# TestPoints.net
KiCad netlist of a schematic drawn in Altium Designer
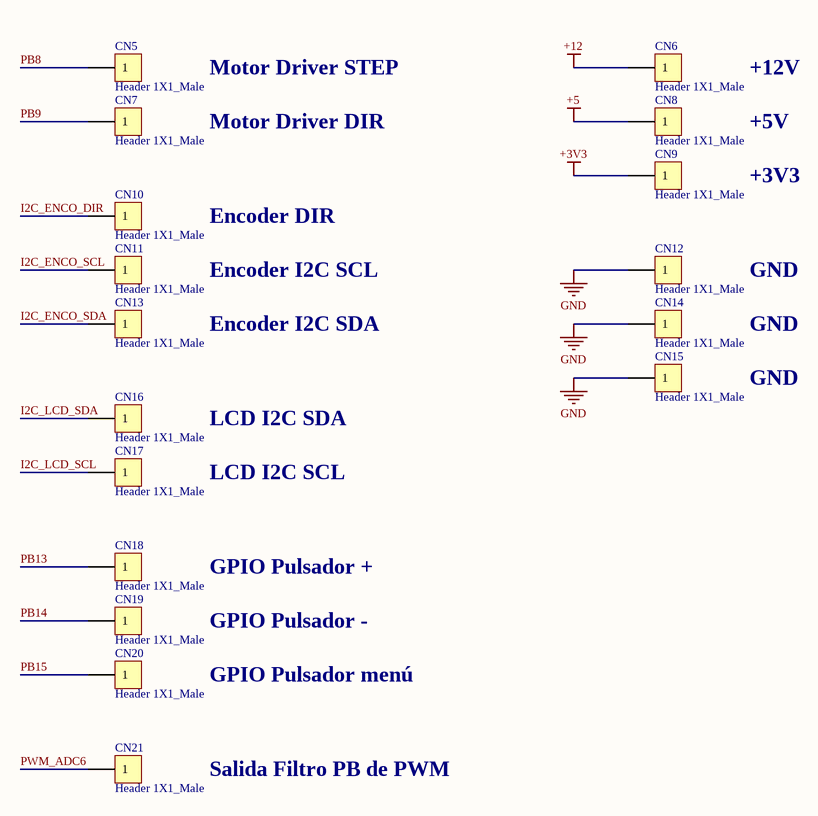
[diagram p0: TestPoints.SchDoc]

(export (version "E")
  (design (tool "Eeschema 10.0.6"))
  (components
    (comp (ref "CN5")
      (value "Header 1X1_Male")
      (footprint "1*1P_MALE")
      (description "Header, 1-Pin, Single row,male")
      (fields (field (name "PUBLISHER") "Altium Limited"))
      (libsource (lib "ProyectoTD3") (part "Header 1X1_Male"))
    )
    (comp (ref "CN6")
      (value "Header 1X1_Male")
      (footprint "1*1P_MALE")
      (description "Header, 1-Pin, Single row,male")
      (fields (field (name "PUBLISHER") "Altium Limited"))
      (libsource (lib "ProyectoTD3") (part "Header 1X1_Male"))
    )
    (comp (ref "CN7")
      (value "Header 1X1_Male")
      (footprint "1*1P_MALE")
      (description "Header, 1-Pin, Single row,male")
      (fields (field (name "PUBLISHER") "Altium Limited"))
      (libsource (lib "ProyectoTD3") (part "Header 1X1_Male"))
    )
    (comp (ref "CN8")
      (value "Header 1X1_Male")
      (footprint "1*1P_MALE")
      (description "Header, 1-Pin, Single row,male")
      (fields (field (name "PUBLISHER") "Altium Limited"))
      (libsource (lib "ProyectoTD3") (part "Header 1X1_Male"))
    )
    (comp (ref "CN9")
      (value "Header 1X1_Male")
      (footprint "1*1P_MALE")
      (description "Header, 1-Pin, Single row,male")
      (fields (field (name "PUBLISHER") "Altium Limited"))
      (libsource (lib "ProyectoTD3") (part "Header 1X1_Male"))
    )
    (comp (ref "CN10")
      (value "Header 1X1_Male")
      (footprint "1*1P_MALE")
      (description "Header, 1-Pin, Single row,male")
      (fields (field (name "PUBLISHER") "Altium Limited"))
      (libsource (lib "ProyectoTD3") (part "Header 1X1_Male"))
    )
    (comp (ref "CN11")
      (value "Header 1X1_Male")
      (footprint "1*1P_MALE")
      (description "Header, 1-Pin, Single row,male")
      (fields (field (name "PUBLISHER") "Altium Limited"))
      (libsource (lib "ProyectoTD3") (part "Header 1X1_Male"))
    )
    (comp (ref "CN12")
      (value "Header 1X1_Male")
      (footprint "1*1P_MALE")
      (description "Header, 1-Pin, Single row,male")
      (fields (field (name "PUBLISHER") "Altium Limited"))
      (libsource (lib "ProyectoTD3") (part "Header 1X1_Male"))
    )
    (comp (ref "CN13")
      (value "Header 1X1_Male")
      (footprint "1*1P_MALE")
      (description "Header, 1-Pin, Single row,male")
      (fields (field (name "PUBLISHER") "Altium Limited"))
      (libsource (lib "ProyectoTD3") (part "Header 1X1_Male"))
    )
    (comp (ref "CN14")
      (value "Header 1X1_Male")
      (footprint "1*1P_MALE")
      (description "Header, 1-Pin, Single row,male")
      (fields (field (name "PUBLISHER") "Altium Limited"))
      (libsource (lib "ProyectoTD3") (part "Header 1X1_Male"))
    )
    (comp (ref "CN15")
      (value "Header 1X1_Male")
      (footprint "1*1P_MALE")
      (description "Header, 1-Pin, Single row,male")
      (fields (field (name "PUBLISHER") "Altium Limited"))
      (libsource (lib "ProyectoTD3") (part "Header 1X1_Male"))
    )
    (comp (ref "CN16")
      (value "Header 1X1_Male")
      (footprint "1*1P_MALE")
      (description "Header, 1-Pin, Single row,male")
      (fields (field (name "PUBLISHER") "Altium Limited"))
      (libsource (lib "ProyectoTD3") (part "Header 1X1_Male"))
    )
    (comp (ref "CN17")
      (value "Header 1X1_Male")
      (footprint "1*1P_MALE")
      (description "Header, 1-Pin, Single row,male")
      (fields (field (name "PUBLISHER") "Altium Limited"))
      (libsource (lib "ProyectoTD3") (part "Header 1X1_Male"))
    )
    (comp (ref "CN18")
      (value "Header 1X1_Male")
      (footprint "1*1P_MALE")
      (description "Header, 1-Pin, Single row,male")
      (fields (field (name "PUBLISHER") "Altium Limited"))
      (libsource (lib "ProyectoTD3") (part "Header 1X1_Male"))
    )
    (comp (ref "CN19")
      (value "Header 1X1_Male")
      (footprint "1*1P_MALE")
      (description "Header, 1-Pin, Single row,male")
      (fields (field (name "PUBLISHER") "Altium Limited"))
      (libsource (lib "ProyectoTD3") (part "Header 1X1_Male"))
    )
    (comp (ref "CN20")
      (value "Header 1X1_Male")
      (footprint "1*1P_MALE")
      (description "Header, 1-Pin, Single row,male")
      (fields (field (name "PUBLISHER") "Altium Limited"))
      (libsource (lib "ProyectoTD3") (part "Header 1X1_Male"))
    )
    (comp (ref "CN21")
      (value "Header 1X1_Male")
      (footprint "1*1P_MALE")
      (description "Header, 1-Pin, Single row,male")
      (fields (field (name "PUBLISHER") "Altium Limited"))
      (libsource (lib "ProyectoTD3") (part "Header 1X1_Male"))
    )
  )
  (nets
    (net (code "1") (name "+3V3") (class "Default")
      (node (ref "CN9") (pin "1") (pinfunction "1_1") (pintype "passive"))
    )
    (net (code "2") (name "+5") (class "Default")
      (node (ref "CN8") (pin "1") (pinfunction "1_1") (pintype "passive"))
    )
    (net (code "3") (name "+12") (class "Default")
      (node (ref "CN6") (pin "1") (pinfunction "1_1") (pintype "passive"))
    )
    (net (code "4") (name "/I2C_ENCO_DIR") (class "Default")
      (node (ref "CN10") (pin "1") (pinfunction "1_1") (pintype "passive"))
    )
    (net (code "5") (name "/I2C_ENCO_SCL") (class "Default")
      (node (ref "CN11") (pin "1") (pinfunction "1_1") (pintype "passive"))
    )
    (net (code "6") (name "/I2C_ENCO_SDA") (class "Default")
      (node (ref "CN13") (pin "1") (pinfunction "1_1") (pintype "passive"))
    )
    (net (code "7") (name "/I2C_LCD_SCL") (class "Default")
      (node (ref "CN17") (pin "1") (pinfunction "1_1") (pintype "passive"))
    )
    (net (code "8") (name "/I2C_LCD_SDA") (class "Default")
      (node (ref "CN16") (pin "1") (pinfunction "1_1") (pintype "passive"))
    )
    (net (code "9") (name "/PB8") (class "Default")
      (node (ref "CN5") (pin "1") (pinfunction "1_1") (pintype "passive"))
    )
    (net (code "10") (name "/PB9") (class "Default")
      (node (ref "CN7") (pin "1") (pinfunction "1_1") (pintype "passive"))
    )
    (net (code "11") (name "/PB13") (class "Default")
      (node (ref "CN18") (pin "1") (pinfunction "1_1") (pintype "passive"))
    )
    (net (code "12") (name "/PB14") (class "Default")
      (node (ref "CN19") (pin "1") (pinfunction "1_1") (pintype "passive"))
    )
    (net (code "13") (name "/PB15") (class "Default")
      (node (ref "CN20") (pin "1") (pinfunction "1_1") (pintype "passive"))
    )
    (net (code "14") (name "/PWM_ADC6") (class "Default")
      (node (ref "CN21") (pin "1") (pinfunction "1_1") (pintype "passive"))
    )
    (net (code "15") (name "GND") (class "Default")
      (node (ref "CN12") (pin "1") (pinfunction "1_1") (pintype "passive"))
      (node (ref "CN14") (pin "1") (pinfunction "1_1") (pintype "passive"))
      (node (ref "CN15") (pin "1") (pinfunction "1_1") (pintype "passive"))
    )
  )
)
